# stm32balance.net
KiCad netlist of a schematic drawn in Altium Designer
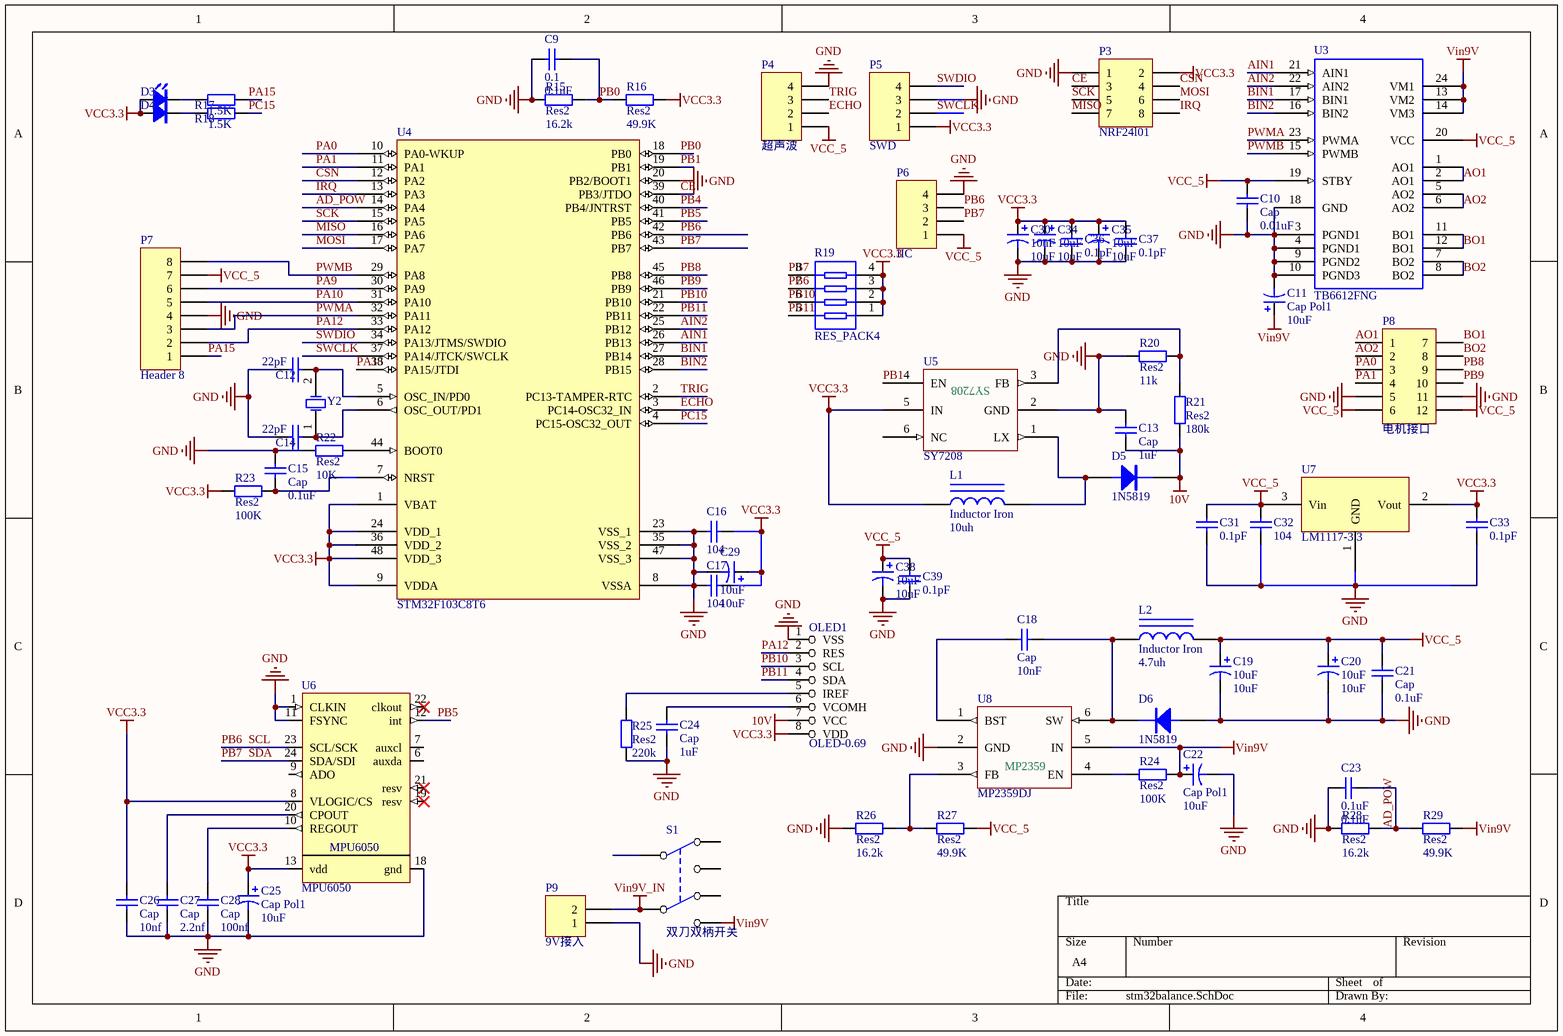
[diagram p0: stm32balance.SchDoc]

(export (version "E")
  (design (tool "Eeschema 10.0.6"))
  (components
    (comp (ref "C9")
      (value "0.1")
      (footprint "LC-0603_C")
      (description "Capacitor")
      (fields (field (name "ALTIUM_VALUE") "0.1uF") (field (name "PUBLISHER") "Altium Limited"))
      (libsource (lib "Miscellaneous Devices") (part "Cap"))
    )
    (comp (ref "C10")
      (value "Cap")
      (footprint "LC-0805_C")
      (description "Capacitor")
      (fields (field (name "ALTIUM_VALUE") "0.01uF") (field (name "PUBLISHER") "Altium Limited"))
      (libsource (lib "Miscellaneous Devices") (part "Cap"))
    )
    (comp (ref "C11")
      (value "Cap Pol1")
      (footprint "电容HONOR_63X54")
      (description "Polarized Capacitor (Radial)")
      (fields (field (name "ALTIUM_VALUE") "10uF") (field (name "PUBLISHER") "Altium Limited"))
      (libsource (lib "Miscellaneous Devices") (part "Cap Pol1"))
    )
    (comp (ref "C12")
      (value "22pF")
      (footprint "LC-0603_C")
      (fields (field (name "Comment") "CAP"))
      (libsource (lib "MySchLib") (part "CAP"))
    )
    (comp (ref "C13")
      (value "Cap")
      (footprint "LC-0603_C")
      (description "Capacitor")
      (fields (field (name "ALTIUM_VALUE") "1uF") (field (name "PUBLISHER") "Altium Limited"))
      (libsource (lib "Miscellaneous Devices") (part "Cap"))
    )
    (comp (ref "C14")
      (value "22pF")
      (footprint "LC-0603_C")
      (fields (field (name "Comment") "CAP"))
      (libsource (lib "MySchLib") (part "CAP"))
    )
    (comp (ref "C15")
      (value "Cap")
      (footprint "LC-0603_C")
      (description "Capacitor")
      (fields (field (name "ALTIUM_VALUE") "0.1uF") (field (name "PUBLISHER") "Altium Limited"))
      (libsource (lib "Miscellaneous Devices") (part "Cap"))
    )
    (comp (ref "C16")
      (value "104")
      (footprint "LC-0603_C")
      (description "Capacitor")
      (fields (field (name "Comment") "Cap") (field (name "PUBLISHER") "Altium Limited"))
      (libsource (lib "Miscellaneous Devices") (part "Cap"))
    )
    (comp (ref "C17")
      (value "104")
      (footprint "LC-0603_C")
      (description "Capacitor")
      (fields (field (name "Comment") "Cap") (field (name "PUBLISHER") "Altium Limited"))
      (libsource (lib "Miscellaneous Devices") (part "Cap"))
    )
    (comp (ref "C18")
      (value "Cap")
      (footprint "LC-0603_C")
      (description "Capacitor")
      (fields (field (name "ALTIUM_VALUE") "10nF") (field (name "PUBLISHER") "Altium Limited"))
      (libsource (lib "Miscellaneous Devices") (part "Cap"))
    )
    (comp (ref "C19")
      (value "10uF")
      (footprint "LC-1210_C")
      (description "Polarized Capacitor (Radial)")
      (fields (field (name "ALTIUM_VALUE") "10uF") (field (name "PUBLISHER") "Altium Limited"))
      (libsource (lib "Miscellaneous Devices") (part "Cap Pol1"))
    )
    (comp (ref "C20")
      (value "10uF")
      (footprint "电容HONOR_63X77")
      (description "Polarized Capacitor (Radial)")
      (fields (field (name "ALTIUM_VALUE") "10uF") (field (name "PUBLISHER") "Altium Limited"))
      (libsource (lib "Miscellaneous Devices") (part "Cap Pol1"))
    )
    (comp (ref "C21")
      (value "Cap")
      (footprint "LC-0603_C")
      (description "Capacitor")
      (fields (field (name "ALTIUM_VALUE") "0.1uF") (field (name "PUBLISHER") "Altium Limited"))
      (libsource (lib "Miscellaneous Devices") (part "Cap"))
    )
    (comp (ref "C22")
      (value "Cap Pol1")
      (footprint "电容HONOR_63X54")
      (description "Polarized Capacitor (Radial)")
      (fields (field (name "ALTIUM_VALUE") "10uF") (field (name "PUBLISHER") "Altium Limited"))
      (libsource (lib "Miscellaneous Devices") (part "Cap Pol1"))
    )
    (comp (ref "C23")
      (value "0.1uF")
      (footprint "LC-0603_C")
      (description "Capacitor")
      (fields (field (name "ALTIUM_VALUE") "0.1uF") (field (name "PUBLISHER") "Altium Limited"))
      (libsource (lib "Miscellaneous Devices") (part "Cap"))
    )
    (comp (ref "C24")
      (value "Cap")
      (footprint "LC-0603_C")
      (description "Capacitor")
      (fields (field (name "ALTIUM_VALUE") "1uF") (field (name "PUBLISHER") "Altium Limited"))
      (libsource (lib "Miscellaneous Devices") (part "Cap"))
    )
    (comp (ref "C25")
      (value "Cap Pol1")
      (footprint "LC-1210_C")
      (description "Polarized Capacitor (Radial)")
      (fields (field (name "ALTIUM_VALUE") "10uF") (field (name "PUBLISHER") "Altium Limited"))
      (libsource (lib "Miscellaneous Devices") (part "Cap Pol1"))
    )
    (comp (ref "C26")
      (value "Cap")
      (footprint "LC-0603_C")
      (description "Capacitor")
      (fields (field (name "ALTIUM_VALUE") "10nf") (field (name "PUBLISHER") "Altium Limited"))
      (libsource (lib "Miscellaneous Devices") (part "Cap"))
    )
    (comp (ref "C27")
      (value "Cap")
      (footprint "LC-0603_C")
      (description "Capacitor")
      (fields (field (name "ALTIUM_VALUE") "2.2nf") (field (name "PUBLISHER") "Altium Limited"))
      (libsource (lib "Miscellaneous Devices") (part "Cap"))
    )
    (comp (ref "C28")
      (value "Cap")
      (footprint "LC-0603_C")
      (description "Capacitor")
      (fields (field (name "ALTIUM_VALUE") "100nf") (field (name "PUBLISHER") "Altium Limited"))
      (libsource (lib "Miscellaneous Devices") (part "Cap"))
    )
    (comp (ref "C29")
      (value "10uF")
      (footprint "LC-1210_C")
      (description "Polarized Capacitor (Radial)")
      (fields (field (name "ALTIUM_VALUE") "10uF") (field (name "PUBLISHER") "Altium Limited"))
      (libsource (lib "Miscellaneous Devices") (part "Cap Pol1"))
    )
    (comp (ref "C30")
      (value "10uF")
      (footprint "电容HONOR_63X77")
      (description "Polarized Capacitor (Radial)")
      (fields (field (name "ALTIUM_VALUE") "10uF") (field (name "PUBLISHER") "Altium Limited"))
      (libsource (lib "Miscellaneous Devices") (part "Cap Pol1"))
    )
    (comp (ref "C31")
      (value "0.1pF")
      (footprint "LC-0603_C")
      (description "Capacitor")
      (fields (field (name "Comment") "Cap") (field (name "PUBLISHER") "Altium Limited"))
      (libsource (lib "Miscellaneous Devices") (part "Cap"))
    )
    (comp (ref "C32")
      (value "104")
      (footprint "LC-Standard-FootPrints-AD-V1.00:LC-1210_C")
      (description "Capacitor")
      (fields (field (name "Comment") "Cap") (field (name "PUBLISHER") "Altium Limited"))
      (libsource (lib "Miscellaneous Devices") (part "Cap"))
    )
    (comp (ref "C33")
      (value "0.1pF")
      (footprint "LC-0603_C")
      (description "Capacitor")
      (fields (field (name "Comment") "Cap") (field (name "PUBLISHER") "Altium Limited"))
      (libsource (lib "Miscellaneous Devices") (part "Cap"))
    )
    (comp (ref "C34")
      (value "10uF")
      (footprint "LC-1210_C")
      (description "Polarized Capacitor (Radial)")
      (fields (field (name "ALTIUM_VALUE") "10uF") (field (name "PUBLISHER") "Altium Limited"))
      (libsource (lib "Miscellaneous Devices") (part "Cap Pol1"))
    )
    (comp (ref "C35")
      (value "10uF")
      (footprint "LC-1210_C")
      (description "Polarized Capacitor (Radial)")
      (fields (field (name "ALTIUM_VALUE") "10uF") (field (name "PUBLISHER") "Altium Limited"))
      (libsource (lib "Miscellaneous Devices") (part "Cap Pol1"))
    )
    (comp (ref "C36")
      (value "0.1pF")
      (footprint "LC-0603_C")
      (description "Capacitor")
      (fields (field (name "Comment") "Cap") (field (name "PUBLISHER") "Altium Limited"))
      (libsource (lib "Miscellaneous Devices") (part "Cap"))
    )
    (comp (ref "C37")
      (value "0.1pF")
      (footprint "LC-0603_C")
      (description "Capacitor")
      (fields (field (name "Comment") "Cap") (field (name "PUBLISHER") "Altium Limited"))
      (libsource (lib "Miscellaneous Devices") (part "Cap"))
    )
    (comp (ref "C38")
      (value "10uF")
      (footprint "LC-1210_C")
      (description "Polarized Capacitor (Radial)")
      (fields (field (name "ALTIUM_VALUE") "10uF") (field (name "PUBLISHER") "Altium Limited"))
      (libsource (lib "Miscellaneous Devices") (part "Cap Pol1"))
    )
    (comp (ref "C39")
      (value "0.1pF")
      (footprint "LC-0603_C")
      (description "Capacitor")
      (fields (field (name "Comment") "Cap") (field (name "PUBLISHER") "Altium Limited"))
      (libsource (lib "Miscellaneous Devices") (part "Cap"))
    )
    (comp (ref "D3") (value "LED") (footprint "LC-0805_LED") (libsource (lib "MySchLib_1") (part "LED")))
    (comp (ref "D4") (value "LED") (footprint "LC-0805_LED") (libsource (lib "MySchLib_1") (part "LED")))
    (comp (ref "D5") (value "1N5819") (footprint "LC-0805_LED") (libsource (lib "ARAMYLIB") (part "1N4001")))
    (comp (ref "D6") (value "1N5819") (footprint "SMA") (libsource (lib "ARAMYLIB") (part "1N4001")))
    (comp (ref "L1")
      (value "Inductor Iron")
      (footprint "LC-0805_L")
      (description "Magnetic-Core Inductor")
      (fields (field (name "ALTIUM_VALUE") "10uh") (field (name "PUBLISHER") "Altium Limited"))
      (libsource (lib "Miscellaneous Devices") (part "Inductor Iron"))
    )
    (comp (ref "L2")
      (value "Inductor Iron")
      (footprint "电感GDCD4532")
      (description "Magnetic-Core Inductor")
      (fields (field (name "ALTIUM_VALUE") "4.7uh") (field (name "PUBLISHER") "Altium Limited"))
      (libsource (lib "Miscellaneous Devices") (part "Inductor Iron"))
    )
    (comp (ref "OLED1")
      (value "OLED-0.69")
      (footprint "OLED-0.69")
      (libsource (lib "ARAMYLIB") (part "OLED-0.69"))
    )
    (comp (ref "P3")
      (value "NRF24l01")
      (footprint "HDR2X4")
      (description "Header, 4-Pin, Dual row")
      (fields (field (name "PUBLISHER") "Altium Limited"))
      (libsource (lib "Miscellaneous Connectors") (part "Header 4X2"))
    )
    (comp (ref "P4")
      (value "超声波")
      (footprint "HDR1X4")
      (description "Header, 4-Pin")
      (fields (field (name "PUBLISHER") "Altium Limited"))
      (libsource (lib "Miscellaneous Connectors") (part "Header 4"))
    )
    (comp (ref "P5")
      (value "SWD")
      (footprint "HDR1X4")
      (description "Header, 4-Pin")
      (fields (field (name "PUBLISHER") "Altium Limited"))
      (libsource (lib "Miscellaneous Connectors") (part "Header 4"))
    )
    (comp (ref "P6")
      (value "IIC")
      (footprint "HDR1X4")
      (description "Header, 4-Pin")
      (fields (field (name "PUBLISHER") "Altium Limited"))
      (libsource (lib "Miscellaneous Connectors") (part "Header 4"))
    )
    (comp (ref "P7")
      (value "Header 8")
      (footprint "HDR1X8")
      (description "Header, 8-Pin")
      (fields (field (name "PUBLISHER") "Altium Limited"))
      (libsource (lib "Miscellaneous Connectors") (part "Header 8"))
    )
    (comp (ref "P8")
      (value "电机接口")
      (footprint "HDR2X6_CEN")
      (description "Header, 6-Pin, Dual row")
      (fields (field (name "PUBLISHER") "Altium Limited"))
      (libsource (lib "Miscellaneous Connectors") (part "Header 6X2A"))
    )
    (comp (ref "P9")
      (value "9V接入")
      (footprint "HDR1X2")
      (description "Header, 2-Pin, Right Angle")
      (fields (field (name "PUBLISHER") "Altium Limited"))
      (libsource (lib "Miscellaneous Connectors") (part "Header 2H"))
    )
    (comp (ref "R15")
      (value "Res2")
      (footprint "LC-0603_R")
      (description "Resistor")
      (fields (field (name "ALTIUM_VALUE") "16.2k") (field (name "PUBLISHER") "Altium Limited"))
      (libsource (lib "Miscellaneous Devices") (part "Res2"))
    )
    (comp (ref "R16")
      (value "Res2")
      (footprint "150PF")
      (description "Resistor")
      (fields (field (name "ALTIUM_VALUE") "49.9K") (field (name "PUBLISHER") "Altium Limited"))
      (libsource (lib "Miscellaneous Devices") (part "Res2"))
    )
    (comp (ref "R17")
      (value "1.5K")
      (footprint "LC-0603_R")
      (description "Resistor")
      (fields (field (name "Comment") "Res2") (field (name "PUBLISHER") "Altium Limited"))
      (libsource (lib "MySchLib") (part "Res2"))
    )
    (comp (ref "R18")
      (value "1.5K")
      (footprint "LC-0603_R")
      (description "Resistor")
      (fields (field (name "Comment") "Res2") (field (name "PUBLISHER") "Altium Limited"))
      (libsource (lib "MySchLib") (part "Res2"))
    )
    (comp (ref "R19") (value "RES_PACK4") (footprint "RES4") (libsource (lib "ARAMYLIB") (part "RES_PACK4")))
    (comp (ref "R20")
      (value "Res2")
      (footprint "LC-0603_R")
      (description "Resistor")
      (fields (field (name "ALTIUM_VALUE") "11k") (field (name "PUBLISHER") "Altium Limited"))
      (libsource (lib "Miscellaneous Devices") (part "Res2"))
    )
    (comp (ref "R21")
      (value "Res2")
      (footprint "LC-0603_R")
      (description "Resistor")
      (fields (field (name "ALTIUM_VALUE") "180k") (field (name "PUBLISHER") "Altium Limited"))
      (libsource (lib "") (part "Res2_1"))
    )
    (comp (ref "R22")
      (value "Res2")
      (footprint "LC-0603_R")
      (description "Resistor")
      (fields (field (name "ALTIUM_VALUE") "10K") (field (name "PUBLISHER") "Altium Limited"))
      (libsource (lib "") (part "Res2_2"))
    )
    (comp (ref "R23")
      (value "Res2")
      (footprint "LC-0603_R")
      (description "Resistor")
      (fields (field (name "ALTIUM_VALUE") "100K") (field (name "PUBLISHER") "Altium Limited"))
      (libsource (lib "") (part "Res2_2"))
    )
    (comp (ref "R24")
      (value "Res2")
      (footprint "LC-0603_R")
      (description "Resistor")
      (fields (field (name "ALTIUM_VALUE") "100K") (field (name "PUBLISHER") "Altium Limited"))
      (libsource (lib "") (part "Res2_2"))
    )
    (comp (ref "R25")
      (value "Res2")
      (footprint "LC-0603_R")
      (description "Resistor")
      (fields (field (name "ALTIUM_VALUE") "220k") (field (name "PUBLISHER") "Altium Limited"))
      (libsource (lib "") (part "Res2_1"))
    )
    (comp (ref "R26")
      (value "Res2")
      (footprint "LC-0603_R")
      (description "Resistor")
      (fields (field (name "ALTIUM_VALUE") "16.2k") (field (name "PUBLISHER") "Altium Limited"))
      (libsource (lib "Miscellaneous Devices") (part "Res2"))
    )
    (comp (ref "R27")
      (value "Res2")
      (footprint "LC-0603_R")
      (description "Resistor")
      (fields (field (name "ALTIUM_VALUE") "49.9K") (field (name "PUBLISHER") "Altium Limited"))
      (libsource (lib "Miscellaneous Devices") (part "Res2"))
    )
    (comp (ref "R28")
      (value "Res2")
      (footprint "LC-0603_R")
      (description "Resistor")
      (fields (field (name "ALTIUM_VALUE") "16.2k") (field (name "PUBLISHER") "Altium Limited"))
      (libsource (lib "Miscellaneous Devices") (part "Res2"))
    )
    (comp (ref "R29")
      (value "Res2")
      (footprint "LC-0603_R")
      (description "Resistor")
      (fields (field (name "ALTIUM_VALUE") "49.9K") (field (name "PUBLISHER") "Altium Limited"))
      (libsource (lib "Miscellaneous Devices") (part "Res2"))
    )
    (comp (ref "S1") (value "双刀双柄开关") (footprint "8*8自锁开关") (libsource (lib "ARAMYLIB") (part "双刀双柄开关")))
    (comp (ref "U3") (value "TB6612FNG") (footprint "SSOP24") (libsource (lib "ARAMYLIB") (part "TB6612FNG")))
    (comp (ref "U4")
      (value "STM32F103C8T6")
      (footprint "LQFP48_L")
      (description "STM32 ARM-based 32-bit MCU with 64 Kbytes Flash, 48-pin LQFP, Industrial Temperature")
      (fields (field (name "PUBLISHER") "Altium Limited"))
      (libsource (lib "ST Microcontroller 32-Bit STM32") (part "STM32F103C8T6"))
    )
    (comp (ref "U5") (value "SY7208") (footprint "LC-SOT-23-6") (libsource (lib "ARAMYLIB") (part "SY7208")))
    (comp (ref "U6") (value "MPU6050") (footprint "qfn24") (libsource (lib "aramy_四轴") (part "MPU6050")))
    (comp (ref "U7")
      (value "LM1117-3.3")
      (footprint "SOT223")
      (libsource (lib "MySchLib") (part "LM1117-3.3"))
    )
    (comp (ref "U8") (value "MP2359DJ") (footprint "SOT23-6") (libsource (lib "ARAMYLIB") (part "MP2359DJ")))
    (comp (ref "Y2")
      (value "12MHz")
      (footprint "49SMD")
      (description "Crystal Oscillator")
      (fields (field (name "PUBLISHER") "Altium Limited"))
      (libsource (lib "ALIENTEK_底板封装库") (part "XTAL"))
    )
  )
  (nets
    (net (code "1") (name "/AD_POW") (class "Default")
      (node (ref "C23") (pin "1") (pinfunction "1_1") (pintype "passive"))
      (node (ref "R28") (pin "1") (pinfunction "1_1") (pintype "passive"))
      (node (ref "R29") (pin "2") (pinfunction "2_2") (pintype "passive"))
      (node (ref "U4") (pin "14") (pinfunction "PA4_14") (pintype "bidirectional"))
    )
    (net (code "2") (name "/AIN1") (class "Default")
      (node (ref "U3") (pin "21") (pinfunction "AIN1_21") (pintype "input"))
      (node (ref "U4") (pin "26") (pinfunction "PB13_26") (pintype "bidirectional"))
    )
    (net (code "3") (name "/AIN2") (class "Default")
      (node (ref "U3") (pin "22") (pinfunction "AIN2_22") (pintype "input"))
      (node (ref "U4") (pin "25") (pinfunction "PB12_25") (pintype "bidirectional"))
    )
    (net (code "4") (name "/AO1") (class "Default")
      (node (ref "P8") (pin "1") (pinfunction "1_1") (pintype "passive"))
      (node (ref "U3") (pin "1") (pinfunction "AO1_1") (pintype "passive"))
      (node (ref "U3") (pin "2") (pinfunction "AO1_2") (pintype "passive"))
    )
    (net (code "5") (name "/AO2") (class "Default")
      (node (ref "P8") (pin "2") (pinfunction "2_2") (pintype "passive"))
      (node (ref "U3") (pin "5") (pinfunction "AO2_5") (pintype "passive"))
      (node (ref "U3") (pin "6") (pinfunction "AO2_6") (pintype "passive"))
    )
    (net (code "6") (name "/BIN1") (class "Default")
      (node (ref "U3") (pin "17") (pinfunction "BIN1_17") (pintype "input"))
      (node (ref "U4") (pin "27") (pinfunction "PB14_27") (pintype "bidirectional"))
    )
    (net (code "7") (name "/BIN2") (class "Default")
      (node (ref "U3") (pin "16") (pinfunction "BIN2_16") (pintype "input"))
      (node (ref "U4") (pin "28") (pinfunction "PB15_28") (pintype "bidirectional"))
    )
    (net (code "8") (name "/BO1") (class "Default")
      (node (ref "P8") (pin "7") (pinfunction "7_7") (pintype "passive"))
      (node (ref "U3") (pin "11") (pinfunction "BO1_11") (pintype "passive"))
      (node (ref "U3") (pin "12") (pinfunction "BO1_12") (pintype "passive"))
    )
    (net (code "9") (name "/BO2") (class "Default")
      (node (ref "P8") (pin "8") (pinfunction "8_8") (pintype "passive"))
      (node (ref "U3") (pin "7") (pinfunction "BO2_7") (pintype "passive"))
      (node (ref "U3") (pin "8") (pinfunction "BO2_8") (pintype "passive"))
    )
    (net (code "10") (name "/CE") (class "Default")
      (node (ref "P3") (pin "3") (pinfunction "3_3") (pintype "passive"))
      (node (ref "U4") (pin "39") (pinfunction "PB3/JTDO_39") (pintype "bidirectional"))
    )
    (net (code "11") (name "/CSN") (class "Default")
      (node (ref "P3") (pin "4") (pinfunction "4_4") (pintype "passive"))
      (node (ref "U4") (pin "12") (pinfunction "PA2_12") (pintype "bidirectional"))
    )
    (net (code "12") (name "/ECHO") (class "Default")
      (node (ref "P4") (pin "2") (pinfunction "2_2") (pintype "passive"))
      (node (ref "U4") (pin "3") (pinfunction "PC14-OSC32_IN_3") (pintype "bidirectional"))
    )
    (net (code "13") (name "/IRQ") (class "Default")
      (node (ref "P3") (pin "8") (pinfunction "8_8") (pintype "passive"))
      (node (ref "U4") (pin "13") (pinfunction "PA3_13") (pintype "bidirectional"))
    )
    (net (code "14") (name "/MISO") (class "Default")
      (node (ref "P3") (pin "7") (pinfunction "7_7") (pintype "passive"))
      (node (ref "U4") (pin "16") (pinfunction "PA6_16") (pintype "bidirectional"))
    )
    (net (code "15") (name "/MOSI") (class "Default")
      (node (ref "P3") (pin "6") (pinfunction "6_6") (pintype "passive"))
      (node (ref "U4") (pin "17") (pinfunction "PA7_17") (pintype "bidirectional"))
    )
    (net (code "16") (name "/PA0") (class "Default")
      (node (ref "P8") (pin "3") (pinfunction "3_3") (pintype "passive"))
      (node (ref "U4") (pin "10") (pinfunction "PA0-WKUP_10") (pintype "bidirectional"))
    )
    (net (code "17") (name "/PA1") (class "Default")
      (node (ref "P8") (pin "4") (pinfunction "4_4") (pintype "passive"))
      (node (ref "U4") (pin "11") (pinfunction "PA1_11") (pintype "bidirectional"))
    )
    (net (code "18") (name "/PA9") (class "Default")
      (node (ref "P7") (pin "6") (pinfunction "6_6") (pintype "passive"))
      (node (ref "U4") (pin "30") (pinfunction "PA9_30") (pintype "bidirectional"))
    )
    (net (code "19") (name "/PA10") (class "Default")
      (node (ref "P7") (pin "5") (pinfunction "5_5") (pintype "passive"))
      (node (ref "U4") (pin "31") (pinfunction "PA10_31") (pintype "bidirectional"))
    )
    (net (code "20") (name "/PA12") (class "Default")
      (node (ref "OLED1") (pin "2") (pinfunction "RES_2") (pintype "passive"))
      (node (ref "P7") (pin "2") (pinfunction "2_2") (pintype "passive"))
      (node (ref "U4") (pin "33") (pinfunction "PA12_33") (pintype "bidirectional"))
    )
    (net (code "21") (name "/PA15") (class "Default")
      (node (ref "P7") (pin "1") (pinfunction "1_1") (pintype "passive"))
      (node (ref "R17") (pin "2") (pinfunction "2_2") (pintype "passive"))
      (node (ref "U4") (pin "38") (pinfunction "PA15/JTDI_38") (pintype "bidirectional"))
    )
    (net (code "22") (name "/PB0") (class "Default")
      (node (ref "C9") (pin "1") (pinfunction "1_1") (pintype "passive"))
      (node (ref "R15") (pin "1") (pinfunction "1_1") (pintype "passive"))
      (node (ref "R16") (pin "2") (pinfunction "2_2") (pintype "passive"))
      (node (ref "U4") (pin "18") (pinfunction "PB0_18") (pintype "bidirectional"))
    )
    (net (code "23") (name "/PB1") (class "Default")
      (node (ref "U4") (pin "19") (pinfunction "PB1_19") (pintype "bidirectional"))
      (node (ref "U5") (pin "4") (pinfunction "EN_4") (pintype "power_in"))
    )
    (net (code "24") (name "/PB4") (class "Default")
      (node (ref "U4") (pin "40") (pinfunction "PB4/JNTRST_40") (pintype "bidirectional"))
    )
    (net (code "25") (name "/PB5") (class "Default")
      (node (ref "U4") (pin "41") (pinfunction "PB5_41") (pintype "bidirectional"))
      (node (ref "U6") (pin "12") (pinfunction "int_12") (pintype "output"))
    )
    (net (code "26") (name "/PB6") (class "Default")
      (node (ref "P6") (pin "3") (pinfunction "3_3") (pintype "passive"))
      (node (ref "R19") (pin "7") (pinfunction "7_7") (pintype "passive"))
      (node (ref "U4") (pin "42") (pinfunction "PB6_42") (pintype "bidirectional"))
      (node (ref "U6") (pin "23") (pinfunction "SCL/SCK_23") (pintype "bidirectional"))
    )
    (net (code "27") (name "/PB7") (class "Default")
      (node (ref "P6") (pin "2") (pinfunction "2_2") (pintype "passive"))
      (node (ref "R19") (pin "8") (pinfunction "8_8") (pintype "passive"))
      (node (ref "U4") (pin "43") (pinfunction "PB7_43") (pintype "bidirectional"))
      (node (ref "U6") (pin "24") (pinfunction "SDA/SDI_24") (pintype "bidirectional"))
    )
    (net (code "28") (name "/PB8") (class "Default")
      (node (ref "P8") (pin "9") (pinfunction "9_9") (pintype "passive"))
      (node (ref "U4") (pin "45") (pinfunction "PB8_45") (pintype "bidirectional"))
    )
    (net (code "29") (name "/PB9") (class "Default")
      (node (ref "P8") (pin "10") (pinfunction "10_10") (pintype "passive"))
      (node (ref "U4") (pin "46") (pinfunction "PB9_46") (pintype "bidirectional"))
    )
    (net (code "30") (name "/PB10") (class "Default")
      (node (ref "OLED1") (pin "3") (pinfunction "SCL_3") (pintype "passive"))
      (node (ref "R19") (pin "6") (pinfunction "6_6") (pintype "passive"))
      (node (ref "U4") (pin "21") (pinfunction "PB10_21") (pintype "bidirectional"))
    )
    (net (code "31") (name "/PB11") (class "Default")
      (node (ref "OLED1") (pin "4") (pinfunction "SDA_4") (pintype "passive"))
      (node (ref "R19") (pin "5") (pinfunction "5_5") (pintype "passive"))
      (node (ref "U4") (pin "22") (pinfunction "PB11_22") (pintype "bidirectional"))
    )
    (net (code "32") (name "/PC15") (class "Default")
      (node (ref "R18") (pin "2") (pinfunction "2_2") (pintype "passive"))
      (node (ref "U4") (pin "4") (pinfunction "PC15-OSC32_OUT_4") (pintype "bidirectional"))
    )
    (net (code "33") (name "/PWMA") (class "Default")
      (node (ref "P7") (pin "3") (pinfunction "3_3") (pintype "passive"))
      (node (ref "U3") (pin "23") (pinfunction "PWMA_23") (pintype "input"))
      (node (ref "U4") (pin "32") (pinfunction "PA11_32") (pintype "bidirectional"))
    )
    (net (code "34") (name "/PWMB") (class "Default")
      (node (ref "P7") (pin "8") (pinfunction "8_8") (pintype "passive"))
      (node (ref "U3") (pin "15") (pinfunction "PWMB_15") (pintype "input"))
      (node (ref "U4") (pin "29") (pinfunction "PA8_29") (pintype "bidirectional"))
    )
    (net (code "35") (name "/SCK") (class "Default")
      (node (ref "P3") (pin "5") (pinfunction "5_5") (pintype "passive"))
      (node (ref "U4") (pin "15") (pinfunction "PA5_15") (pintype "bidirectional"))
    )
    (net (code "36") (name "/SWCLK") (class "Default")
      (node (ref "P5") (pin "2") (pinfunction "2_2") (pintype "passive"))
      (node (ref "U4") (pin "37") (pinfunction "PA14/JTCK/SWCLK_37") (pintype "bidirectional"))
    )
    (net (code "37") (name "/SWDIO") (class "Default")
      (node (ref "P5") (pin "4") (pinfunction "4_4") (pintype "passive"))
      (node (ref "U4") (pin "34") (pinfunction "PA13/JTMS/SWDIO_34") (pintype "bidirectional"))
    )
    (net (code "38") (name "/TRIG") (class "Default")
      (node (ref "P4") (pin "3") (pinfunction "3_3") (pintype "passive"))
      (node (ref "U4") (pin "2") (pinfunction "PC13-TAMPER-RTC_2") (pintype "bidirectional"))
    )
    (net (code "39") (name "10V") (class "Default")
      (node (ref "C13") (pin "1") (pinfunction "1_1") (pintype "passive"))
      (node (ref "D5") (pin "K") (pinfunction "2_K") (pintype "passive"))
      (node (ref "OLED1") (pin "7") (pinfunction "VCC_7") (pintype "power_in"))
      (node (ref "R21") (pin "1") (pinfunction "1_1") (pintype "passive"))
    )
    (net (code "40") (name "GND") (class "Default")
      (node (ref "C10") (pin "2") (pinfunction "2_2") (pintype "passive"))
      (node (ref "C11") (pin "2") (pinfunction "2_2") (pintype "passive"))
      (node (ref "C12") (pin "1") (pinfunction "1_1") (pintype "passive"))
      (node (ref "C13") (pin "2") (pinfunction "2_2") (pintype "passive"))
      (node (ref "C14") (pin "1") (pinfunction "1_1") (pintype "passive"))
      (node (ref "C15") (pin "2") (pinfunction "2_2") (pintype "passive"))
      (node (ref "C16") (pin "2") (pinfunction "2_2") (pintype "passive"))
      (node (ref "C17") (pin "2") (pinfunction "2_2") (pintype "passive"))
      (node (ref "C19") (pin "2") (pinfunction "2_2") (pintype "passive"))
      (node (ref "C20") (pin "2") (pinfunction "2_2") (pintype "passive"))
      (node (ref "C21") (pin "1") (pinfunction "1_1") (pintype "passive"))
      (node (ref "C22") (pin "2") (pinfunction "2_2") (pintype "passive"))
      (node (ref "C23") (pin "2") (pinfunction "2_2") (pintype "passive"))
      (node (ref "C24") (pin "2") (pinfunction "2_2") (pintype "passive"))
      (node (ref "C25") (pin "2") (pinfunction "2_2") (pintype "passive"))
      (node (ref "C26") (pin "1") (pinfunction "1_1") (pintype "passive"))
      (node (ref "C27") (pin "1") (pinfunction "1_1") (pintype "passive"))
      (node (ref "C28") (pin "1") (pinfunction "1_1") (pintype "passive"))
      (node (ref "C29") (pin "2") (pinfunction "2_2") (pintype "passive"))
      (node (ref "C30") (pin "2") (pinfunction "2_2") (pintype "passive"))
      (node (ref "C31") (pin "2") (pinfunction "2_2") (pintype "passive"))
      (node (ref "C32") (pin "1") (pinfunction "1_1") (pintype "passive"))
      (node (ref "C33") (pin "2") (pinfunction "2_2") (pintype "passive"))
      (node (ref "C34") (pin "2") (pinfunction "2_2") (pintype "passive"))
      (node (ref "C35") (pin "2") (pinfunction "2_2") (pintype "passive"))
      (node (ref "C36") (pin "2") (pinfunction "2_2") (pintype "passive"))
      (node (ref "C37") (pin "2") (pinfunction "2_2") (pintype "passive"))
      (node (ref "C38") (pin "2") (pinfunction "2_2") (pintype "passive"))
      (node (ref "C39") (pin "2") (pinfunction "2_2") (pintype "passive"))
      (node (ref "C9") (pin "2") (pinfunction "2_2") (pintype "passive"))
      (node (ref "D6") (pin "A") (pinfunction "1_A") (pintype "passive"))
      (node (ref "OLED1") (pin "1") (pinfunction "VSS_1") (pintype "power_in"))
      (node (ref "P3") (pin "1") (pinfunction "1_1") (pintype "passive"))
      (node (ref "P4") (pin "4") (pinfunction "4_4") (pintype "passive"))
      (node (ref "P5") (pin "3") (pinfunction "3_3") (pintype "passive"))
      (node (ref "P6") (pin "4") (pinfunction "4_4") (pintype "passive"))
      (node (ref "P7") (pin "4") (pinfunction "4_4") (pintype "passive"))
      (node (ref "P8") (pin "11") (pinfunction "11_11") (pintype "passive"))
      (node (ref "P8") (pin "5") (pinfunction "5_5") (pintype "passive"))
      (node (ref "P9") (pin "1") (pinfunction "1_1") (pintype "passive"))
      (node (ref "R15") (pin "2") (pinfunction "2_2") (pintype "passive"))
      (node (ref "R20") (pin "2") (pinfunction "2_2") (pintype "passive"))
      (node (ref "R22") (pin "1") (pinfunction "1_1") (pintype "passive"))
      (node (ref "R25") (pin "1") (pinfunction "1_1") (pintype "passive"))
      (node (ref "R26") (pin "2") (pinfunction "2_2") (pintype "passive"))
      (node (ref "R28") (pin "2") (pinfunction "2_2") (pintype "passive"))
      (node (ref "U3") (pin "10") (pinfunction "PGND3_10") (pintype "power_in"))
      (node (ref "U3") (pin "18") (pinfunction "GND_18") (pintype "power_in"))
      (node (ref "U3") (pin "3") (pinfunction "PGND1_3") (pintype "power_in"))
      (node (ref "U3") (pin "4") (pinfunction "PGND1_4") (pintype "power_in"))
      (node (ref "U3") (pin "9") (pinfunction "PGND2_9") (pintype "power_in"))
      (node (ref "U4") (pin "20") (pinfunction "PB2/BOOT1_20") (pintype "bidirectional"))
      (node (ref "U4") (pin "23") (pinfunction "VSS_1_23") (pintype "power_in"))
      (node (ref "U4") (pin "35") (pinfunction "VSS_2_35") (pintype "power_in"))
      (node (ref "U4") (pin "47") (pinfunction "VSS_3_47") (pintype "power_in"))
      (node (ref "U4") (pin "8") (pinfunction "VSSA_8") (pintype "power_in"))
      (node (ref "U5") (pin "2") (pinfunction "GND_2") (pintype "power_in"))
      (node (ref "U6") (pin "1") (pinfunction "CLKIN_1") (pintype "input"))
      (node (ref "U6") (pin "11") (pinfunction "FSYNC_11") (pintype "bidirectional"))
      (node (ref "U6") (pin "18") (pinfunction "gnd_18") (pintype "power_in"))
      (node (ref "U7") (pin "1") (pinfunction "GND_1") (pintype "passive"))
      (node (ref "U8") (pin "2") (pinfunction "GND_2") (pintype "power_in"))
    )
    (net (code "41") (name "Net-(D3-Pad2)") (class "Default")
      (node (ref "D3") (pin "2") (pinfunction "2_2") (pintype "passive"))
      (node (ref "R17") (pin "1") (pinfunction "1_1") (pintype "passive"))
    )
    (net (code "42") (name "Net-(D4-Pad2)") (class "Default")
      (node (ref "D4") (pin "2") (pinfunction "2_2") (pintype "passive"))
      (node (ref "R18") (pin "1") (pinfunction "1_1") (pintype "passive"))
    )
    (net (code "43") (name "Net-(D5-1)") (class "Default")
      (node (ref "D5") (pin "A") (pinfunction "1_A") (pintype "passive"))
      (node (ref "L1") (pin "2") (pinfunction "2_2") (pintype "passive"))
      (node (ref "U5") (pin "1") (pinfunction "LX_1") (pintype "output"))
    )
    (net (code "44") (name "Net-(D6-2)") (class "Default")
      (node (ref "C18") (pin "2") (pinfunction "2_2") (pintype "passive"))
      (node (ref "D6") (pin "K") (pinfunction "2_K") (pintype "passive"))
      (node (ref "L2") (pin "1") (pinfunction "1_1") (pintype "passive"))
      (node (ref "U8") (pin "6") (pinfunction "SW_6") (pintype "input"))
    )
    (net (code "45") (name "Net-(OLED1-IREF)") (class "Default")
      (node (ref "OLED1") (pin "5") (pinfunction "IREF_5") (pintype "passive"))
      (node (ref "R25") (pin "2") (pinfunction "2_2") (pintype "passive"))
    )
    (net (code "46") (name "Net-(OLED1-VCOMH)") (class "Default")
      (node (ref "C24") (pin "1") (pinfunction "1_1") (pintype "passive"))
      (node (ref "OLED1") (pin "6") (pinfunction "VCOMH_6") (pintype "passive"))
    )
    (net (code "47") (name "Net-(U4-BOOT0)") (class "Default")
      (node (ref "R22") (pin "2") (pinfunction "2_2") (pintype "passive"))
      (node (ref "U4") (pin "44") (pinfunction "BOOT0_44") (pintype "input"))
    )
    (net (code "48") (name "Net-(U4-NRST)") (class "Default")
      (node (ref "C15") (pin "1") (pinfunction "1_1") (pintype "passive"))
      (node (ref "R23") (pin "2") (pinfunction "2_2") (pintype "passive"))
      (node (ref "U4") (pin "7") (pinfunction "NRST_7") (pintype "bidirectional"))
    )
    (net (code "49") (name "Net-(U4-OSC_IN{slash}PD0)") (class "Default")
      (node (ref "C12") (pin "2") (pinfunction "2_2") (pintype "passive"))
      (node (ref "U4") (pin "5") (pinfunction "OSC_IN/PD0_5") (pintype "input"))
      (node (ref "Y2") (pin "2") (pinfunction "OSC2_2") (pintype "passive"))
    )
    (net (code "50") (name "Net-(U4-OSC_OUT{slash}PD1)") (class "Default")
      (node (ref "C14") (pin "2") (pinfunction "2_2") (pintype "passive"))
      (node (ref "U4") (pin "6") (pinfunction "OSC_OUT/PD1_6") (pintype "output"))
      (node (ref "Y2") (pin "1") (pinfunction "OSC1_1") (pintype "passive"))
    )
    (net (code "51") (name "Net-(U5-FB)") (class "Default")
      (node (ref "R20") (pin "1") (pinfunction "1_1") (pintype "passive"))
      (node (ref "R21") (pin "2") (pinfunction "2_2") (pintype "passive"))
      (node (ref "U5") (pin "3") (pinfunction "FB_3") (pintype "output"))
    )
    (net (code "52") (name "Net-(U6-CPOUT)") (class "Default")
      (node (ref "C27") (pin "2") (pinfunction "2_2") (pintype "passive"))
      (node (ref "U6") (pin "20") (pinfunction "CPOUT_20") (pintype "output"))
    )
    (net (code "53") (name "Net-(U6-REGOUT)") (class "Default")
      (node (ref "C28") (pin "2") (pinfunction "2_2") (pintype "passive"))
      (node (ref "U6") (pin "10") (pinfunction "REGOUT_10") (pintype "output"))
    )
    (net (code "54") (name "Net-(U8-BST)") (class "Default")
      (node (ref "C18") (pin "1") (pinfunction "1_1") (pintype "passive"))
      (node (ref "U8") (pin "1") (pinfunction "BST_1") (pintype "output"))
    )
    (net (code "55") (name "Net-(U8-EN)") (class "Default")
      (node (ref "R24") (pin "1") (pinfunction "1_1") (pintype "passive"))
      (node (ref "U8") (pin "4") (pinfunction "EN_4") (pintype "power_in"))
    )
    (net (code "56") (name "Net-(U8-FB)") (class "Default")
      (node (ref "R26") (pin "1") (pinfunction "1_1") (pintype "passive"))
      (node (ref "R27") (pin "2") (pinfunction "2_2") (pintype "passive"))
      (node (ref "U8") (pin "3") (pinfunction "FB_3") (pintype "output"))
    )
    (net (code "57") (name "VCC3.3") (class "Default")
      (node (ref "C16") (pin "1") (pinfunction "1_1") (pintype "passive"))
      (node (ref "C17") (pin "1") (pinfunction "1_1") (pintype "passive"))
      (node (ref "C25") (pin "1") (pinfunction "1_1") (pintype "passive"))
      (node (ref "C26") (pin "2") (pinfunction "2_2") (pintype "passive"))
      (node (ref "C29") (pin "1") (pinfunction "1_1") (pintype "passive"))
      (node (ref "C30") (pin "1") (pinfunction "1_1") (pintype "passive"))
      (node (ref "C33") (pin "1") (pinfunction "1_1") (pintype "passive"))
      (node (ref "C34") (pin "1") (pinfunction "1_1") (pintype "passive"))
      (node (ref "C35") (pin "1") (pinfunction "1_1") (pintype "passive"))
      (node (ref "C36") (pin "1") (pinfunction "1_1") (pintype "passive"))
      (node (ref "C37") (pin "1") (pinfunction "1_1") (pintype "passive"))
      (node (ref "D3") (pin "1") (pinfunction "1_1") (pintype "passive"))
      (node (ref "D4") (pin "1") (pinfunction "1_1") (pintype "passive"))
      (node (ref "L1") (pin "1") (pinfunction "1_1") (pintype "passive"))
      (node (ref "OLED1") (pin "8") (pinfunction "VDD_8") (pintype "power_in"))
      (node (ref "P3") (pin "2") (pinfunction "2_2") (pintype "passive"))
      (node (ref "P5") (pin "1") (pinfunction "1_1") (pintype "passive"))
      (node (ref "R16") (pin "1") (pinfunction "1_1") (pintype "passive"))
      (node (ref "R19") (pin "1") (pinfunction "1_1") (pintype "passive"))
      (node (ref "R19") (pin "2") (pinfunction "2_2") (pintype "passive"))
      (node (ref "R19") (pin "3") (pinfunction "3_3") (pintype "passive"))
      (node (ref "R19") (pin "4") (pinfunction "4_4") (pintype "passive"))
      (node (ref "R23") (pin "1") (pinfunction "1_1") (pintype "passive"))
      (node (ref "U4") (pin "1") (pinfunction "VBAT_1") (pintype "power_in"))
      (node (ref "U4") (pin "24") (pinfunction "VDD_1_24") (pintype "power_in"))
      (node (ref "U4") (pin "36") (pinfunction "VDD_2_36") (pintype "power_in"))
      (node (ref "U4") (pin "48") (pinfunction "VDD_3_48") (pintype "power_in"))
      (node (ref "U4") (pin "9") (pinfunction "VDDA_9") (pintype "power_in"))
      (node (ref "U5") (pin "5") (pinfunction "IN_5") (pintype "power_in"))
      (node (ref "U6") (pin "13") (pinfunction "vdd_13") (pintype "power_in"))
      (node (ref "U6") (pin "8") (pinfunction "VLOGIC/CS_8") (pintype "bidirectional"))
      (node (ref "U7") (pin "2") (pinfunction "Vout_2") (pintype "passive"))
    )
    (net (code "58") (name "VCC_5") (class "Default")
      (node (ref "C10") (pin "1") (pinfunction "1_1") (pintype "passive"))
      (node (ref "C19") (pin "1") (pinfunction "1_1") (pintype "passive"))
      (node (ref "C20") (pin "1") (pinfunction "1_1") (pintype "passive"))
      (node (ref "C21") (pin "2") (pinfunction "2_2") (pintype "passive"))
      (node (ref "C31") (pin "1") (pinfunction "1_1") (pintype "passive"))
      (node (ref "C32") (pin "2") (pinfunction "2_2") (pintype "passive"))
      (node (ref "C38") (pin "1") (pinfunction "1_1") (pintype "passive"))
      (node (ref "C39") (pin "1") (pinfunction "1_1") (pintype "passive"))
      (node (ref "L2") (pin "2") (pinfunction "2_2") (pintype "passive"))
      (node (ref "P4") (pin "1") (pinfunction "1_1") (pintype "passive"))
      (node (ref "P6") (pin "1") (pinfunction "1_1") (pintype "passive"))
      (node (ref "P7") (pin "7") (pinfunction "7_7") (pintype "passive"))
      (node (ref "P8") (pin "12") (pinfunction "12_12") (pintype "passive"))
      (node (ref "P8") (pin "6") (pinfunction "6_6") (pintype "passive"))
      (node (ref "R27") (pin "1") (pinfunction "1_1") (pintype "passive"))
      (node (ref "U3") (pin "19") (pinfunction "STBY_19") (pintype "input"))
      (node (ref "U3") (pin "20") (pinfunction "VCC_20") (pintype "power_in"))
      (node (ref "U7") (pin "3") (pinfunction "Vin_3") (pintype "passive"))
    )
    (net (code "59") (name "Vin9V") (class "Default")
      (node (ref "C11") (pin "1") (pinfunction "1_1") (pintype "passive"))
      (node (ref "C22") (pin "1") (pinfunction "1_1") (pintype "passive"))
      (node (ref "R24") (pin "2") (pinfunction "2_2") (pintype "passive"))
      (node (ref "R29") (pin "1") (pinfunction "1_1") (pintype "passive"))
      (node (ref "S1") (pin "6") (pinfunction "NO2_6") (pintype "passive"))
      (node (ref "U3") (pin "13") (pinfunction "VM2_13") (pintype "power_in"))
      (node (ref "U3") (pin "14") (pinfunction "VM3_14") (pintype "power_in"))
      (node (ref "U3") (pin "24") (pinfunction "VM1_24") (pintype "power_in"))
      (node (ref "U8") (pin "5") (pinfunction "IN_5") (pintype "power_in"))
    )
    (net (code "60") (name "Vin9V_IN") (class "Default")
      (node (ref "P9") (pin "2") (pinfunction "2_2") (pintype "passive"))
      (node (ref "S1") (pin "2") (pinfunction "COMMON2_2") (pintype "passive"))
    )
    (net (code "61") (name "unconnected-(S1-COMMON1-Pad1)") (class "Default")
      (node (ref "S1") (pin "1") (pinfunction "COMMON1_1") (pintype "passive"))
    )
    (net (code "62") (name "unconnected-(S1-NC1-Pad3)") (class "Default")
      (node (ref "S1") (pin "3") (pinfunction "NC1_3") (pintype "passive"))
    )
    (net (code "63") (name "unconnected-(S1-NC2-Pad4)") (class "Default")
      (node (ref "S1") (pin "4") (pinfunction "NC2_4") (pintype "passive"))
    )
    (net (code "64") (name "unconnected-(S1-NO1-Pad5)") (class "Default")
      (node (ref "S1") (pin "5") (pinfunction "NO1_5") (pintype "passive"))
    )
    (net (code "65") (name "unconnected-(U5-NC-Pad6)") (class "Default")
      (node (ref "U5") (pin "6") (pinfunction "NC_6") (pintype "input"))
    )
    (net (code "66") (name "unconnected-(U6-ADO-Pad9)") (class "Default")
      (node (ref "U6") (pin "9") (pinfunction "ADO_9") (pintype "output"))
    )
    (net (code "67") (name "unconnected-(U6-auxcl-Pad7)") (class "Default")
      (node (ref "U6") (pin "7") (pinfunction "auxcl_7") (pintype "bidirectional"))
    )
    (net (code "68") (name "unconnected-(U6-auxda-Pad6)") (class "Default")
      (node (ref "U6") (pin "6") (pinfunction "auxda_6") (pintype "bidirectional"))
    )
    (net (code "69") (name "unconnected-(U6-clkout-Pad22)") (class "Default")
      (node (ref "U6") (pin "22") (pinfunction "clkout_22") (pintype "output+no_connect"))
    )
    (net (code "70") (name "unconnected-(U6-resv-Pad19)") (class "Default")
      (node (ref "U6") (pin "19") (pinfunction "resv_19") (pintype "input+no_connect"))
    )
    (net (code "71") (name "unconnected-(U6-resv-Pad21)") (class "Default")
      (node (ref "U6") (pin "21") (pinfunction "resv_21") (pintype "input+no_connect"))
    )
  )
)
